# RecalLED.net
KiCad netlist of a schematic drawn in EAGLE
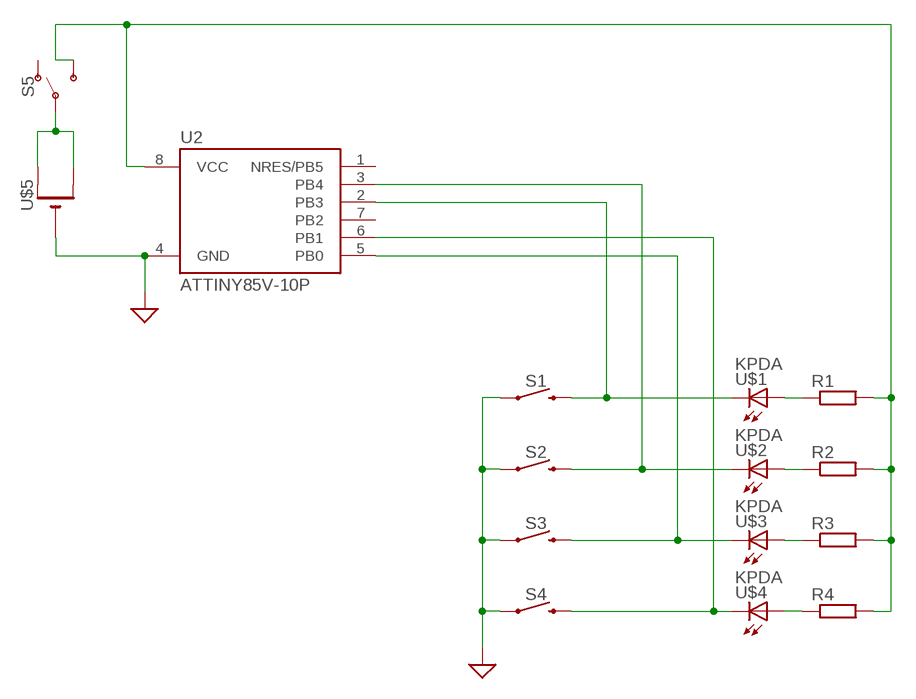
[diagram p0: schematic, sheet 1]

(export (version "E")
  (design (tool "Eeschema 10.0.6"))
  (components
    (comp (ref "R1")
      (value "R-EU_M0805")
      (footprint "eagle-import:M0805")
      (libsource (lib "eagle-import") (part "R-EU_M0805"))
    )
    (comp (ref "R2")
      (value "R-EU_M0805")
      (footprint "eagle-import:M0805")
      (libsource (lib "eagle-import") (part "R-EU_M0805"))
    )
    (comp (ref "R3")
      (value "R-EU_M0805")
      (footprint "eagle-import:M0805")
      (libsource (lib "eagle-import") (part "R-EU_M0805"))
    )
    (comp (ref "R4")
      (value "R-EU_M0805")
      (footprint "eagle-import:M0805")
      (libsource (lib "eagle-import") (part "R-EU_M0805"))
    )
    (comp (ref "S1")
      (value "MOMENTARY-SWITCH-SPST-SMD-6.2MM-TALL")
      (footprint "eagle-import:TACTILE_SWITCH_SMD_6.2MM_TALL")
      (libsource (lib "eagle-import") (part "MOMENTARY-SWITCH-SPST-SMD-6.2MM-TALL"))
    )
    (comp (ref "S2")
      (value "MOMENTARY-SWITCH-SPST-SMD-6.2MM-TALL")
      (footprint "eagle-import:TACTILE_SWITCH_SMD_6.2MM_TALL")
      (libsource (lib "eagle-import") (part "MOMENTARY-SWITCH-SPST-SMD-6.2MM-TALL"))
    )
    (comp (ref "S3")
      (value "MOMENTARY-SWITCH-SPST-SMD-6.2MM-TALL")
      (footprint "eagle-import:TACTILE_SWITCH_SMD_6.2MM_TALL")
      (libsource (lib "eagle-import") (part "MOMENTARY-SWITCH-SPST-SMD-6.2MM-TALL"))
    )
    (comp (ref "S4")
      (value "MOMENTARY-SWITCH-SPST-SMD-6.2MM-TALL")
      (footprint "eagle-import:TACTILE_SWITCH_SMD_6.2MM_TALL")
      (libsource (lib "eagle-import") (part "MOMENTARY-SWITCH-SPST-SMD-6.2MM-TALL"))
    )
    (comp (ref "S5")
      (value "SWITCH-SPDT-SMD-RIGHT-ANGLE")
      (footprint "eagle-import:SWITCH_SPST_SMD_A")
      (libsource (lib "eagle-import") (part "SWITCH-SPDT-SMD-RIGHT-ANGLE"))
    )
    (comp (ref "U$1")
      (value "KPDA")
      (footprint "eagle-import:KPDA")
      (libsource (lib "eagle-import") (part "KPDA"))
    )
    (comp (ref "U$2")
      (value "KPDA")
      (footprint "eagle-import:KPDA")
      (libsource (lib "eagle-import") (part "KPDA"))
    )
    (comp (ref "U$3")
      (value "KPDA")
      (footprint "eagle-import:KPDA")
      (libsource (lib "eagle-import") (part "KPDA"))
    )
    (comp (ref "U$4")
      (value "KPDA")
      (footprint "eagle-import:KPDA")
      (libsource (lib "eagle-import") (part "KPDA"))
    )
    (comp (ref "U$5")
      (value "CR2032SMT")
      (footprint "eagle-import:CR2032-SMD")
      (libsource (lib "eagle-import") (part "CR2032SMT"))
    )
    (comp (ref "U2")
      (value "ATTINY85V-10P")
      (footprint "eagle-import:PDIP08_300MIL")
      (libsource (lib "eagle-import") (part "ATTINY85PV-10"))
    )
  )
  (nets
    (net (code "1") (name "Net-(S1-2)") (class "Default")
      (node (ref "S1") (pin "B2") (pinfunction "2_B2") (pintype "passive"))
      (node (ref "U$1") (pin "P$2") (pinfunction "C_P$2") (pintype "passive"))
      (node (ref "U2") (pin "2") (pinfunction "PB3_2") (pintype "bidirectional"))
    )
    (net (code "2") (name "Net-(S2-2)") (class "Default")
      (node (ref "S2") (pin "B2") (pinfunction "2_B2") (pintype "passive"))
      (node (ref "U$2") (pin "P$2") (pinfunction "C_P$2") (pintype "passive"))
      (node (ref "U2") (pin "3") (pinfunction "PB4_3") (pintype "bidirectional"))
    )
    (net (code "3") (name "Net-(S3-2)") (class "Default")
      (node (ref "S3") (pin "B2") (pinfunction "2_B2") (pintype "passive"))
      (node (ref "U$3") (pin "P$2") (pinfunction "C_P$2") (pintype "passive"))
      (node (ref "U2") (pin "5") (pinfunction "PB0_5") (pintype "bidirectional"))
    )
    (net (code "4") (name "Net-(S4-2)") (class "Default")
      (node (ref "S4") (pin "B2") (pinfunction "2_B2") (pintype "passive"))
      (node (ref "U$4") (pin "P$2") (pinfunction "C_P$2") (pintype "passive"))
      (node (ref "U2") (pin "6") (pinfunction "PB1_6") (pintype "bidirectional"))
    )
    (net (code "5") (name "Net-(S5-P)") (class "Default")
      (node (ref "S5") (pin "2") (pinfunction "P_2") (pintype "passive"))
      (node (ref "U$5") (pin "+$1") (pinfunction "+_+$1") (pintype "passive"))
      (node (ref "U$5") (pin "+$2") (pinfunction "+1_+$2") (pintype "passive"))
    )
    (net (code "6") (name "Net-(S5-S)") (class "Default")
      (node (ref "R1") (pin "2") (pinfunction "2_2") (pintype "passive"))
      (node (ref "R2") (pin "2") (pinfunction "2_2") (pintype "passive"))
      (node (ref "R3") (pin "2") (pinfunction "2_2") (pintype "passive"))
      (node (ref "R4") (pin "2") (pinfunction "2_2") (pintype "passive"))
      (node (ref "S5") (pin "3") (pinfunction "S_3") (pintype "passive"))
      (node (ref "U2") (pin "8") (pinfunction "VCC_8") (pintype "power_in"))
    )
    (net (code "7") (name "Net-(U$1-A)") (class "Default")
      (node (ref "R1") (pin "1") (pinfunction "1_1") (pintype "passive"))
      (node (ref "U$1") (pin "P$1") (pinfunction "A_P$1") (pintype "passive"))
    )
    (net (code "8") (name "Net-(U$2-A)") (class "Default")
      (node (ref "R2") (pin "1") (pinfunction "1_1") (pintype "passive"))
      (node (ref "U$2") (pin "P$1") (pinfunction "A_P$1") (pintype "passive"))
    )
    (net (code "9") (name "Net-(U$3-A)") (class "Default")
      (node (ref "R3") (pin "1") (pinfunction "1_1") (pintype "passive"))
      (node (ref "U$3") (pin "P$1") (pinfunction "A_P$1") (pintype "passive"))
    )
    (net (code "10") (name "Net-(U$4-A)") (class "Default")
      (node (ref "R4") (pin "1") (pinfunction "1_1") (pintype "passive"))
      (node (ref "U$4") (pin "P$1") (pinfunction "A_P$1") (pintype "passive"))
    )
    (net (code "11") (name "SUP") (class "Default")
      (node (ref "S1") (pin "A2") (pinfunction "1_A2") (pintype "passive"))
      (node (ref "S2") (pin "A2") (pinfunction "1_A2") (pintype "passive"))
      (node (ref "S3") (pin "A2") (pinfunction "1_A2") (pintype "passive"))
      (node (ref "S4") (pin "A2") (pinfunction "1_A2") (pintype "passive"))
      (node (ref "U$5") (pin "-") (pinfunction "-_-") (pintype "passive"))
      (node (ref "U2") (pin "4") (pinfunction "GND_4") (pintype "power_in"))
    )
    (net (code "12") (name "unconnected-(S5-O-Pad1)") (class "Default")
      (node (ref "S5") (pin "1") (pinfunction "O_1") (pintype "passive"))
    )
    (net (code "13") (name "unconnected-(U2-NRES{slash}PB5-Pad1)") (class "Default")
      (node (ref "U2") (pin "1") (pinfunction "NRES/PB5_1") (pintype "bidirectional"))
    )
    (net (code "14") (name "unconnected-(U2-PB2-Pad7)") (class "Default")
      (node (ref "U2") (pin "7") (pinfunction "PB2_7") (pintype "bidirectional"))
    )
  )
)
